# BLE_--_HM-10_--_Breakout_v0_9_9.net
KiCad netlist of a schematic drawn in EAGLE
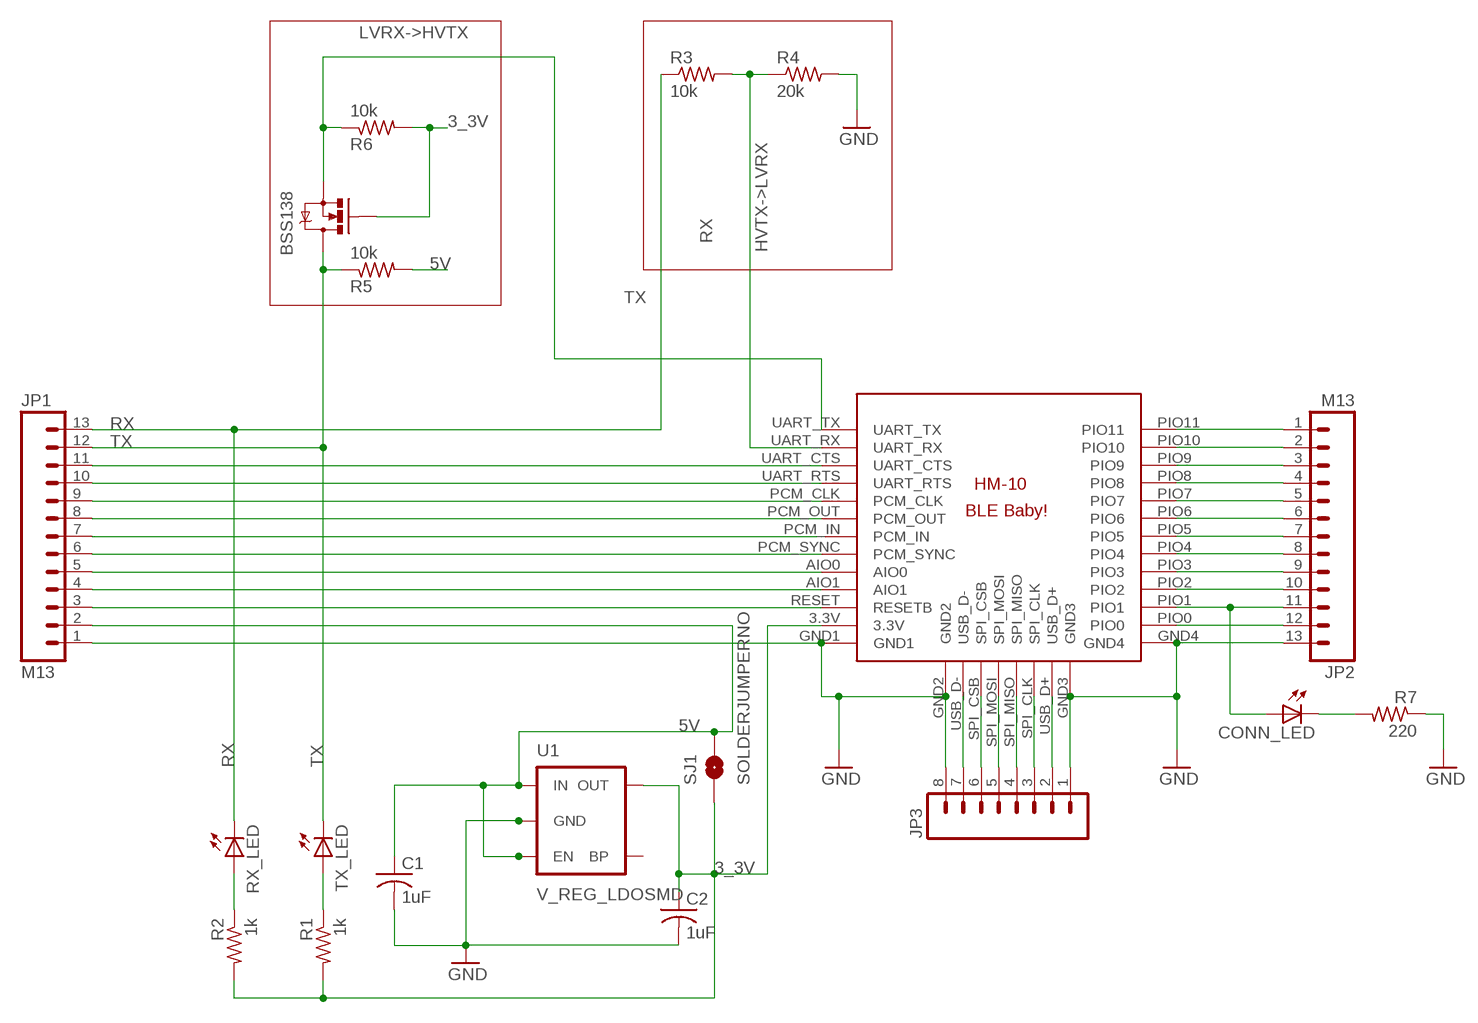
[diagram p0: schematic, sheet 1]

(export (version "E")
  (design (tool "Eeschema 10.0.6"))
  (components
    (comp (ref "BSS138")
      (value "MOSFET-NCHANNELSMD")
      (footprint "eagle-import:SOT23-3")
      (libsource (lib "eagle-import") (part "MOSFET-NCHANNELSMD"))
    )
    (comp (ref "C1")
      (value "1uF")
      (footprint "eagle-import:C0805K")
      (libsource (lib "eagle-import") (part "C-USC0805K"))
    )
    (comp (ref "C2")
      (value "1uF")
      (footprint "eagle-import:C0805K")
      (libsource (lib "eagle-import") (part "C-USC0805K"))
    )
    (comp (ref "CONN_LED")
      (value "LED0603")
      (footprint "eagle-import:LED-0603")
      (libsource (lib "eagle-import") (part "LED0603"))
    )
    (comp (ref "JP1")
      (value "M13")
      (footprint "eagle-import:1X13")
      (libsource (lib "eagle-import") (part "M13"))
    )
    (comp (ref "JP2")
      (value "M13")
      (footprint "eagle-import:1X13")
      (libsource (lib "eagle-import") (part "M13"))
    )
    (comp (ref "JP3")
      (value "M081X08")
      (footprint "eagle-import:1X08")
      (libsource (lib "eagle-import") (part "M081X08"))
    )
    (comp (ref "R1")
      (value "1k")
      (footprint "eagle-import:M0805")
      (libsource (lib "eagle-import") (part "R-US_M0805"))
    )
    (comp (ref "R2")
      (value "1k")
      (footprint "eagle-import:M0805")
      (libsource (lib "eagle-import") (part "R-US_M0805"))
    )
    (comp (ref "R3")
      (value "10k")
      (footprint "eagle-import:M0805")
      (libsource (lib "eagle-import") (part "R-US_M0805"))
    )
    (comp (ref "R4")
      (value "20k")
      (footprint "eagle-import:M0805")
      (libsource (lib "eagle-import") (part "R-US_M0805"))
    )
    (comp (ref "R5")
      (value "10k")
      (footprint "eagle-import:M0805")
      (libsource (lib "eagle-import") (part "R-US_M0805"))
    )
    (comp (ref "R6")
      (value "10k")
      (footprint "eagle-import:M0805")
      (libsource (lib "eagle-import") (part "R-US_M0805"))
    )
    (comp (ref "R7")
      (value "220")
      (footprint "eagle-import:M0805")
      (libsource (lib "eagle-import") (part "R-US_M0805"))
    )
    (comp (ref "RX_LED")
      (value "LED0603")
      (footprint "eagle-import:LED-0603")
      (libsource (lib "eagle-import") (part "LED0603"))
    )
    (comp (ref "SJ1")
      (value "SOLDERJUMPERNO")
      (footprint "eagle-import:SJ_2S-NO")
      (libsource (lib "eagle-import") (part "SOLDERJUMPERNO"))
    )
    (comp (ref "TX_LED")
      (value "LED0603")
      (footprint "eagle-import:LED-0603")
      (libsource (lib "eagle-import") (part "LED0603"))
    )
    (comp (ref "U$1")
      (value "BLE-HM-10")
      (footprint "eagle-import:BLE-HM-10")
      (libsource (lib "eagle-import") (part "BLE-HM-10"))
    )
    (comp (ref "U1")
      (value "V_REG_LDOSMD")
      (footprint "eagle-import:SOT23-5")
      (libsource (lib "eagle-import") (part "V_REG_LDOSMD"))
    )
  )
  (nets
    (net (code "1") (name "/3_3V") (class "Default")
      (node (ref "BSS138") (pin "1") (pinfunction "G_1") (pintype "passive"))
      (node (ref "C2") (pin "1") (pinfunction "1_1") (pintype "passive"))
      (node (ref "R1") (pin "2") (pinfunction "2_2") (pintype "passive"))
      (node (ref "R2") (pin "2") (pinfunction "2_2") (pintype "passive"))
      (node (ref "R6") (pin "2") (pinfunction "2_2") (pintype "passive"))
      (node (ref "SJ1") (pin "1") (pinfunction "1_1") (pintype "passive"))
      (node (ref "U$1") (pin "3.3V") (pinfunction "3.3V_3.3V") (pintype "bidirectional"))
      (node (ref "U1") (pin "5") (pinfunction "OUT_5") (pintype "passive"))
    )
    (net (code "2") (name "/5V") (class "Default")
      (node (ref "C1") (pin "1") (pinfunction "1_1") (pintype "passive"))
      (node (ref "JP1") (pin "2") (pinfunction "2_2") (pintype "passive"))
      (node (ref "R5") (pin "2") (pinfunction "2_2") (pintype "passive"))
      (node (ref "SJ1") (pin "2") (pinfunction "2_2") (pintype "passive"))
      (node (ref "U1") (pin "1") (pinfunction "IN_1") (pintype "input"))
      (node (ref "U1") (pin "3") (pinfunction "EN_3") (pintype "input"))
    )
    (net (code "3") (name "/HVTX->LVRX") (class "Default")
      (node (ref "R3") (pin "2") (pinfunction "2_2") (pintype "passive"))
      (node (ref "R4") (pin "1") (pinfunction "1_1") (pintype "passive"))
      (node (ref "U$1") (pin "UART_RX") (pinfunction "UART_RX_UART_RX") (pintype "bidirectional"))
    )
    (net (code "4") (name "/LVRX->HVTX") (class "Default")
      (node (ref "BSS138") (pin "2") (pinfunction "S_2") (pintype "passive"))
      (node (ref "R6") (pin "1") (pinfunction "1_1") (pintype "passive"))
      (node (ref "U$1") (pin "UART_TX") (pinfunction "UART_TX_UART_TX") (pintype "bidirectional"))
    )
    (net (code "5") (name "/RX") (class "Default")
      (node (ref "JP1") (pin "13") (pinfunction "13_13") (pintype "passive"))
      (node (ref "R3") (pin "1") (pinfunction "1_1") (pintype "passive"))
      (node (ref "RX_LED") (pin "C") (pinfunction "C_C") (pintype "passive"))
    )
    (net (code "6") (name "/TX") (class "Default")
      (node (ref "BSS138") (pin "3") (pinfunction "D_3") (pintype "passive"))
      (node (ref "JP1") (pin "12") (pinfunction "12_12") (pintype "passive"))
      (node (ref "R5") (pin "1") (pinfunction "1_1") (pintype "passive"))
      (node (ref "TX_LED") (pin "C") (pinfunction "C_C") (pintype "passive"))
    )
    (net (code "7") (name "GND") (class "Default")
      (node (ref "C1") (pin "2") (pinfunction "2_2") (pintype "passive"))
      (node (ref "C2") (pin "2") (pinfunction "2_2") (pintype "passive"))
      (node (ref "JP1") (pin "1") (pinfunction "1_1") (pintype "passive"))
      (node (ref "JP2") (pin "13") (pinfunction "13_13") (pintype "passive"))
      (node (ref "JP3") (pin "1") (pinfunction "1_1") (pintype "passive"))
      (node (ref "JP3") (pin "8") (pinfunction "8_8") (pintype "passive"))
      (node (ref "R4") (pin "2") (pinfunction "2_2") (pintype "passive"))
      (node (ref "R7") (pin "1") (pinfunction "1_1") (pintype "passive"))
      (node (ref "U$1") (pin "GND1") (pinfunction "GND1_GND1") (pintype "bidirectional"))
      (node (ref "U$1") (pin "GND2") (pinfunction "GND2_GND2") (pintype "bidirectional"))
      (node (ref "U$1") (pin "GND3") (pinfunction "GND3_GND3") (pintype "bidirectional"))
      (node (ref "U$1") (pin "GND4") (pinfunction "GND4_GND4") (pintype "bidirectional"))
      (node (ref "U1") (pin "2") (pinfunction "GND_2") (pintype "input"))
    )
    (net (code "8") (name "Net-(CONN_LED-PadA)") (class "Default")
      (node (ref "CONN_LED") (pin "A") (pinfunction "A_A") (pintype "passive"))
      (node (ref "JP2") (pin "11") (pinfunction "11_11") (pintype "passive"))
      (node (ref "U$1") (pin "PIO1") (pinfunction "PIO1_PIO1") (pintype "bidirectional"))
    )
    (net (code "9") (name "Net-(CONN_LED-PadC)") (class "Default")
      (node (ref "CONN_LED") (pin "C") (pinfunction "C_C") (pintype "passive"))
      (node (ref "R7") (pin "2") (pinfunction "2_2") (pintype "passive"))
    )
    (net (code "10") (name "Net-(JP1-Pad4)") (class "Default")
      (node (ref "JP1") (pin "4") (pinfunction "4_4") (pintype "passive"))
      (node (ref "U$1") (pin "AIO1") (pinfunction "AIO1_AIO1") (pintype "bidirectional"))
    )
    (net (code "11") (name "Net-(JP1-Pad5)") (class "Default")
      (node (ref "JP1") (pin "5") (pinfunction "5_5") (pintype "passive"))
      (node (ref "U$1") (pin "AIO0") (pinfunction "AIO0_AIO0") (pintype "bidirectional"))
    )
    (net (code "12") (name "Net-(JP1-Pad6)") (class "Default")
      (node (ref "JP1") (pin "6") (pinfunction "6_6") (pintype "passive"))
      (node (ref "U$1") (pin "PCM_SYNC") (pinfunction "PCM_SYNC_PCM_SYNC") (pintype "bidirectional"))
    )
    (net (code "13") (name "Net-(JP1-Pad7)") (class "Default")
      (node (ref "JP1") (pin "7") (pinfunction "7_7") (pintype "passive"))
      (node (ref "U$1") (pin "PCM_IN") (pinfunction "PCM_IN_PCM_IN") (pintype "bidirectional"))
    )
    (net (code "14") (name "Net-(JP1-Pad8)") (class "Default")
      (node (ref "JP1") (pin "8") (pinfunction "8_8") (pintype "passive"))
      (node (ref "U$1") (pin "PCM_OUT") (pinfunction "PCM_OUT_PCM_OUT") (pintype "bidirectional"))
    )
    (net (code "15") (name "Net-(JP1-Pad9)") (class "Default")
      (node (ref "JP1") (pin "9") (pinfunction "9_9") (pintype "passive"))
      (node (ref "U$1") (pin "PCM_CLK") (pinfunction "PCM_CLK_PCM_CLK") (pintype "bidirectional"))
    )
    (net (code "16") (name "Net-(JP1-Pad10)") (class "Default")
      (node (ref "JP1") (pin "10") (pinfunction "10_10") (pintype "passive"))
      (node (ref "U$1") (pin "UART_RTS") (pinfunction "UART_RTS_UART_RTS") (pintype "bidirectional"))
    )
    (net (code "17") (name "Net-(JP1-Pad11)") (class "Default")
      (node (ref "JP1") (pin "11") (pinfunction "11_11") (pintype "passive"))
      (node (ref "U$1") (pin "UART_CTS") (pinfunction "UART_CTS_UART_CTS") (pintype "bidirectional"))
    )
    (net (code "18") (name "Net-(JP2-Pad1)") (class "Default")
      (node (ref "JP2") (pin "1") (pinfunction "1_1") (pintype "passive"))
      (node (ref "U$1") (pin "PIO11") (pinfunction "PIO11_PIO11") (pintype "bidirectional"))
    )
    (net (code "19") (name "Net-(JP2-Pad2)") (class "Default")
      (node (ref "JP2") (pin "2") (pinfunction "2_2") (pintype "passive"))
      (node (ref "U$1") (pin "PIO10") (pinfunction "PIO10_PIO10") (pintype "bidirectional"))
    )
    (net (code "20") (name "Net-(JP2-Pad3)") (class "Default")
      (node (ref "JP2") (pin "3") (pinfunction "3_3") (pintype "passive"))
      (node (ref "U$1") (pin "PIO9") (pinfunction "PIO9_PIO9") (pintype "bidirectional"))
    )
    (net (code "21") (name "Net-(JP2-Pad4)") (class "Default")
      (node (ref "JP2") (pin "4") (pinfunction "4_4") (pintype "passive"))
      (node (ref "U$1") (pin "PIO8") (pinfunction "PIO8_PIO8") (pintype "bidirectional"))
    )
    (net (code "22") (name "Net-(JP2-Pad5)") (class "Default")
      (node (ref "JP2") (pin "5") (pinfunction "5_5") (pintype "passive"))
      (node (ref "U$1") (pin "PIO7") (pinfunction "PIO7_PIO7") (pintype "bidirectional"))
    )
    (net (code "23") (name "Net-(JP2-Pad6)") (class "Default")
      (node (ref "JP2") (pin "6") (pinfunction "6_6") (pintype "passive"))
      (node (ref "U$1") (pin "PIO6") (pinfunction "PIO6_PIO6") (pintype "bidirectional"))
    )
    (net (code "24") (name "Net-(JP2-Pad7)") (class "Default")
      (node (ref "JP2") (pin "7") (pinfunction "7_7") (pintype "passive"))
      (node (ref "U$1") (pin "PIO5") (pinfunction "PIO5_PIO5") (pintype "bidirectional"))
    )
    (net (code "25") (name "Net-(JP2-Pad8)") (class "Default")
      (node (ref "JP2") (pin "8") (pinfunction "8_8") (pintype "passive"))
      (node (ref "U$1") (pin "PIO4") (pinfunction "PIO4_PIO4") (pintype "bidirectional"))
    )
    (net (code "26") (name "Net-(JP2-Pad9)") (class "Default")
      (node (ref "JP2") (pin "9") (pinfunction "9_9") (pintype "passive"))
      (node (ref "U$1") (pin "PIO3") (pinfunction "PIO3_PIO3") (pintype "bidirectional"))
    )
    (net (code "27") (name "Net-(JP2-Pad10)") (class "Default")
      (node (ref "JP2") (pin "10") (pinfunction "10_10") (pintype "passive"))
      (node (ref "U$1") (pin "PIO2") (pinfunction "PIO2_PIO2") (pintype "bidirectional"))
    )
    (net (code "28") (name "Net-(JP2-Pad12)") (class "Default")
      (node (ref "JP2") (pin "12") (pinfunction "12_12") (pintype "passive"))
      (node (ref "U$1") (pin "PIO0") (pinfunction "PIO0_PIO0") (pintype "bidirectional"))
    )
    (net (code "29") (name "Net-(JP3-Pad2)") (class "Default")
      (node (ref "JP3") (pin "2") (pinfunction "2_2") (pintype "passive"))
      (node (ref "U$1") (pin "USB_D+") (pinfunction "USB_D+_USB_D+") (pintype "bidirectional"))
    )
    (net (code "30") (name "Net-(JP3-Pad3)") (class "Default")
      (node (ref "JP3") (pin "3") (pinfunction "3_3") (pintype "passive"))
      (node (ref "U$1") (pin "SPI_CLK") (pinfunction "SPI_CLK_SPI_CLK") (pintype "bidirectional"))
    )
    (net (code "31") (name "Net-(JP3-Pad4)") (class "Default")
      (node (ref "JP3") (pin "4") (pinfunction "4_4") (pintype "passive"))
      (node (ref "U$1") (pin "SPI_MISO") (pinfunction "SPI_MISO_SPI_MISO") (pintype "bidirectional"))
    )
    (net (code "32") (name "Net-(JP3-Pad5)") (class "Default")
      (node (ref "JP3") (pin "5") (pinfunction "5_5") (pintype "passive"))
      (node (ref "U$1") (pin "SPI_MOSI") (pinfunction "SPI_MOSI_SPI_MOSI") (pintype "bidirectional"))
    )
    (net (code "33") (name "Net-(JP3-Pad6)") (class "Default")
      (node (ref "JP3") (pin "6") (pinfunction "6_6") (pintype "passive"))
      (node (ref "U$1") (pin "SPI_CSB") (pinfunction "SPI_CSB_SPI_CSB") (pintype "bidirectional"))
    )
    (net (code "34") (name "Net-(JP3-Pad7)") (class "Default")
      (node (ref "JP3") (pin "7") (pinfunction "7_7") (pintype "passive"))
      (node (ref "U$1") (pin "USB_D-") (pinfunction "USB_D-_USB_D-") (pintype "bidirectional"))
    )
    (net (code "35") (name "Net-(R1-Pad1)") (class "Default")
      (node (ref "R1") (pin "1") (pinfunction "1_1") (pintype "passive"))
      (node (ref "TX_LED") (pin "A") (pinfunction "A_A") (pintype "passive"))
    )
    (net (code "36") (name "Net-(R2-Pad1)") (class "Default")
      (node (ref "R2") (pin "1") (pinfunction "1_1") (pintype "passive"))
      (node (ref "RX_LED") (pin "A") (pinfunction "A_A") (pintype "passive"))
    )
    (net (code "37") (name "Net-(U$1-RESETB)") (class "Default")
      (node (ref "JP1") (pin "3") (pinfunction "3_3") (pintype "passive"))
      (node (ref "U$1") (pin "RESET") (pinfunction "RESETB_RESET") (pintype "bidirectional"))
    )
    (net (code "38") (name "unconnected-(U1-BP-Pad4)") (class "Default")
      (node (ref "U1") (pin "4") (pinfunction "BP_4") (pintype "input"))
    )
  )
)
